# EMMC_Flash_memory.net
KiCad netlist of a schematic drawn in Altium Designer
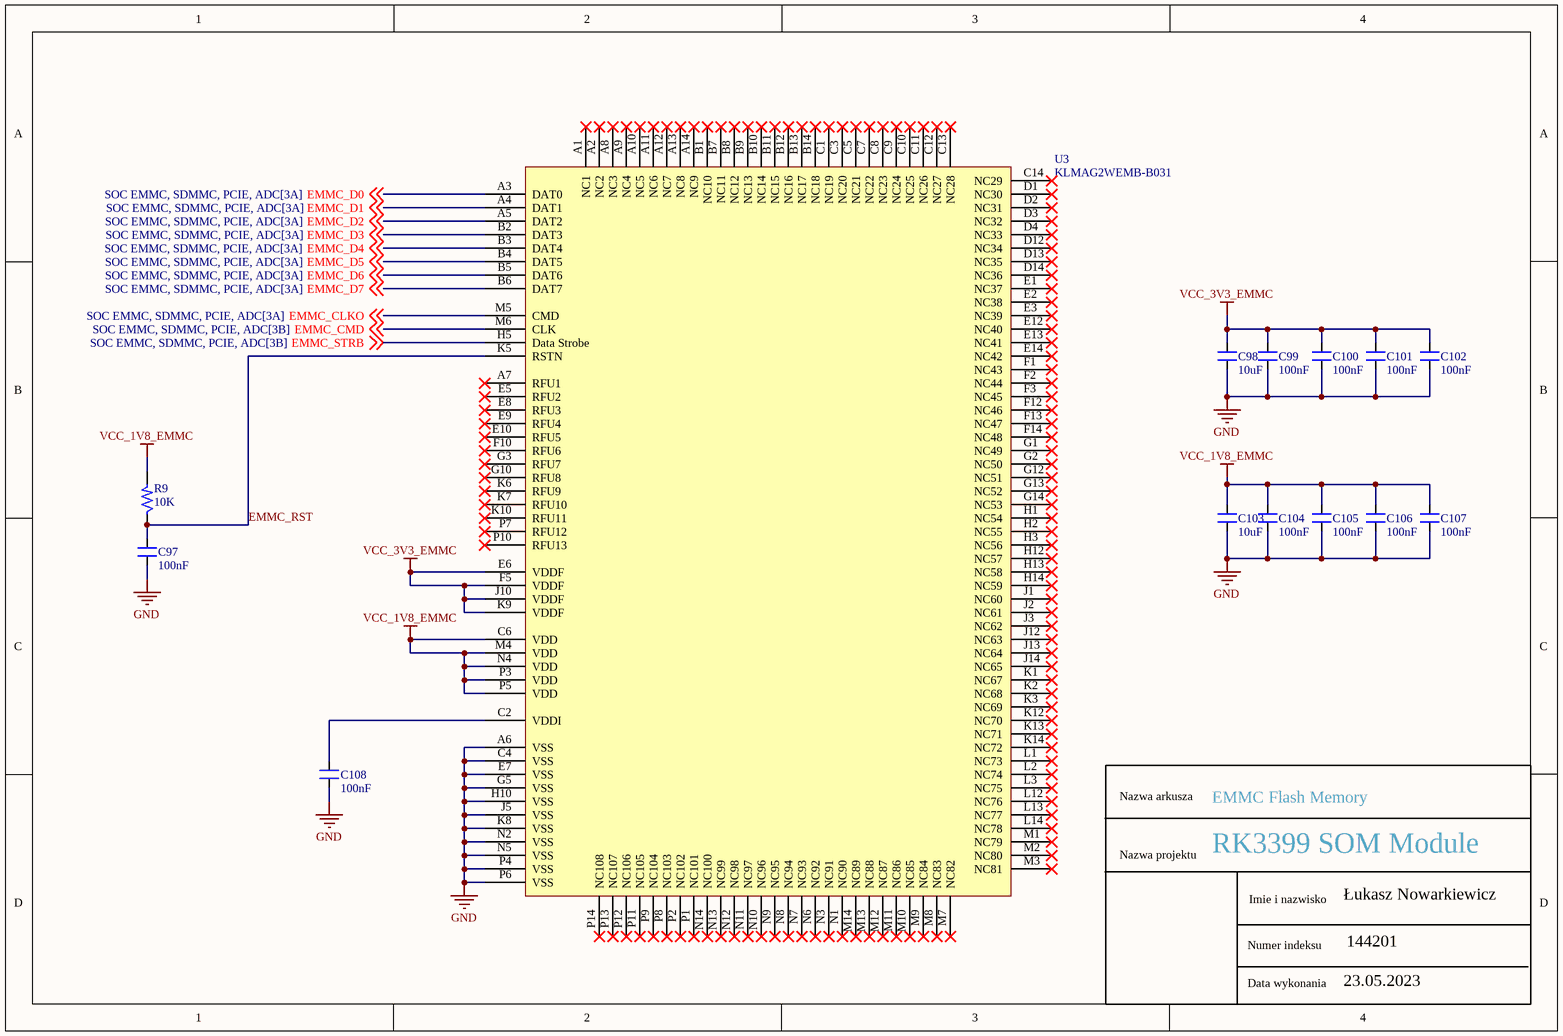
[diagram p0: EMMC Flash memory.SchDoc]

(export (version "E")
  (design (tool "Eeschema 10.0.6"))
  (components
    (comp (ref "C97")
      (value "100nF")
      (footprint "CAP_0402")
      (description "0.1µF ±10% 10V Ceramic Capacitor X7R 0402 (1005 Metric)")
      (fields
        (field (name "MANUFACTURER") "Yageo")
        (field (name "MANUFACTURER PART NUMBER") "CC0402KRX7R6BB104")
      )
      (libsource (lib "EsteemPCB_SOM_Course_intlib") (part "CAP_100nF-10V-10%-0402"))
    )
    (comp (ref "C98")
      (value "10uF")
      (footprint "CAP_0603")
      (description "10µF ±10% 10V Ceramic Capacitor X5R 0603 (1608 Metric)")
      (fields
        (field (name "MANUFACTURER PART NUMBER") "GRM188R61A106KE69J")
        (field (name "MANUFACTURER") "Murata Electronics")
      )
      (libsource (lib "EsteemPCB_SOM_Course_intlib") (part "CAP_10uF-10V-10%-0603"))
    )
    (comp (ref "C99")
      (value "100nF")
      (footprint "CAP_0402")
      (description "0.1µF ±10% 10V Ceramic Capacitor X7R 0402 (1005 Metric)")
      (fields
        (field (name "MANUFACTURER") "Yageo")
        (field (name "MANUFACTURER PART NUMBER") "CC0402KRX7R6BB104")
      )
      (libsource (lib "EsteemPCB_SOM_Course_intlib") (part "CAP_100nF-10V-10%-0402"))
    )
    (comp (ref "C100")
      (value "100nF")
      (footprint "CAP_0402")
      (description "0.1µF ±10% 10V Ceramic Capacitor X7R 0402 (1005 Metric)")
      (fields
        (field (name "MANUFACTURER") "Yageo")
        (field (name "MANUFACTURER PART NUMBER") "CC0402KRX7R6BB104")
      )
      (libsource (lib "EsteemPCB_SOM_Course_intlib") (part "CAP_100nF-10V-10%-0402"))
    )
    (comp (ref "C101")
      (value "100nF")
      (footprint "CAP_0402")
      (description "0.1µF ±10% 10V Ceramic Capacitor X7R 0402 (1005 Metric)")
      (fields
        (field (name "MANUFACTURER") "Yageo")
        (field (name "MANUFACTURER PART NUMBER") "CC0402KRX7R6BB104")
      )
      (libsource (lib "EsteemPCB_SOM_Course_intlib") (part "CAP_100nF-10V-10%-0402"))
    )
    (comp (ref "C102")
      (value "100nF")
      (footprint "CAP_0402")
      (description "0.1µF ±10% 10V Ceramic Capacitor X7R 0402 (1005 Metric)")
      (fields
        (field (name "MANUFACTURER") "Yageo")
        (field (name "MANUFACTURER PART NUMBER") "CC0402KRX7R6BB104")
      )
      (libsource (lib "EsteemPCB_SOM_Course_intlib") (part "CAP_100nF-10V-10%-0402"))
    )
    (comp (ref "C103")
      (value "10uF")
      (footprint "CAP_0603")
      (description "10µF ±10% 10V Ceramic Capacitor X5R 0603 (1608 Metric)")
      (fields
        (field (name "MANUFACTURER PART NUMBER") "GRM188R61A106KE69J")
        (field (name "MANUFACTURER") "Murata Electronics")
      )
      (libsource (lib "EsteemPCB_SOM_Course_intlib") (part "CAP_10uF-10V-10%-0603"))
    )
    (comp (ref "C104")
      (value "100nF")
      (footprint "CAP_0402")
      (description "0.1µF ±10% 10V Ceramic Capacitor X7R 0402 (1005 Metric)")
      (fields
        (field (name "MANUFACTURER") "Yageo")
        (field (name "MANUFACTURER PART NUMBER") "CC0402KRX7R6BB104")
      )
      (libsource (lib "EsteemPCB_SOM_Course_intlib") (part "CAP_100nF-10V-10%-0402"))
    )
    (comp (ref "C105")
      (value "100nF")
      (footprint "CAP_0402")
      (description "0.1µF ±10% 10V Ceramic Capacitor X7R 0402 (1005 Metric)")
      (fields
        (field (name "MANUFACTURER") "Yageo")
        (field (name "MANUFACTURER PART NUMBER") "CC0402KRX7R6BB104")
      )
      (libsource (lib "EsteemPCB_SOM_Course_intlib") (part "CAP_100nF-10V-10%-0402"))
    )
    (comp (ref "C106")
      (value "100nF")
      (footprint "CAP_0402")
      (description "0.1µF ±10% 10V Ceramic Capacitor X7R 0402 (1005 Metric)")
      (fields
        (field (name "MANUFACTURER") "Yageo")
        (field (name "MANUFACTURER PART NUMBER") "CC0402KRX7R6BB104")
      )
      (libsource (lib "EsteemPCB_SOM_Course_intlib") (part "CAP_100nF-10V-10%-0402"))
    )
    (comp (ref "C107")
      (value "100nF")
      (footprint "CAP_0402")
      (description "0.1µF ±10% 10V Ceramic Capacitor X7R 0402 (1005 Metric)")
      (fields
        (field (name "MANUFACTURER") "Yageo")
        (field (name "MANUFACTURER PART NUMBER") "CC0402KRX7R6BB104")
      )
      (libsource (lib "EsteemPCB_SOM_Course_intlib") (part "CAP_100nF-10V-10%-0402"))
    )
    (comp (ref "C108")
      (value "100nF")
      (footprint "CAP_0402")
      (description "0.1µF ±10% 10V Ceramic Capacitor X7R 0402 (1005 Metric)")
      (fields
        (field (name "MANUFACTURER") "Yageo")
        (field (name "MANUFACTURER PART NUMBER") "CC0402KRX7R6BB104")
      )
      (libsource (lib "EsteemPCB_SOM_Course_intlib") (part "CAP_100nF-10V-10%-0402"))
    )
    (comp (ref "R9")
      (value "10K")
      (footprint "RES_0201")
      (description "10 kOhms ±1% 0.05W, 1/20W Chip Resistor 0201 (0603 Metric) Thick Film")
      (fields
        (field (name "MANUFACTURER") "Stackpole Electronics Inc")
        (field (name "MANUFACTURER PART NUMBER") "RMCF0201FT10K0")
      )
      (libsource (lib "EsteemPCB_SOM_Course_intlib") (part "RES_10K-0.05W-1%-0201"))
    )
    (comp (ref "U3")
      (value "KLMAG2WEMB-B031")
      (footprint "BGA153C50P14X14_1150X1300X70")
      (description "16GB NAND Flash Memory")
      (fields (field (name "MANUFACTURER") "Samsung Electronics"))
      (libsource (lib "EsteemPCB_SOM_Course_intlib") (part "IC_KLMAG2WEMB-B031"))
    )
  )
  (nets
    (net (code "1") (name "/EMMC_RST") (class "Default")
      (node (ref "C97") (pin "2") (pinfunction "2_2") (pintype "passive"))
      (node (ref "R9") (pin "1") (pinfunction "1_1") (pintype "passive"))
      (node (ref "U3") (pin "K5") (pinfunction "RSTN_K5") (pintype "passive"))
    )
    (net (code "2") (name "EMMC_CLKO") (class "Default")
      (node (ref "U3") (pin "M5") (pinfunction "CMD_M5") (pintype "passive"))
    )
    (net (code "3") (name "EMMC_CMD") (class "Default")
      (node (ref "U3") (pin "M6") (pinfunction "CLK_M6") (pintype "passive"))
    )
    (net (code "4") (name "EMMC_D0") (class "Default")
      (node (ref "U3") (pin "A3") (pinfunction "DAT0_A3") (pintype "passive"))
    )
    (net (code "5") (name "EMMC_D1") (class "Default")
      (node (ref "U3") (pin "A4") (pinfunction "DAT1_A4") (pintype "passive"))
    )
    (net (code "6") (name "EMMC_D2") (class "Default")
      (node (ref "U3") (pin "A5") (pinfunction "DAT2_A5") (pintype "passive"))
    )
    (net (code "7") (name "EMMC_D3") (class "Default")
      (node (ref "U3") (pin "B2") (pinfunction "DAT3_B2") (pintype "passive"))
    )
    (net (code "8") (name "EMMC_D4") (class "Default")
      (node (ref "U3") (pin "B3") (pinfunction "DAT4_B3") (pintype "passive"))
    )
    (net (code "9") (name "EMMC_D5") (class "Default")
      (node (ref "U3") (pin "B4") (pinfunction "DAT5_B4") (pintype "passive"))
    )
    (net (code "10") (name "EMMC_D6") (class "Default")
      (node (ref "U3") (pin "B5") (pinfunction "DAT6_B5") (pintype "passive"))
    )
    (net (code "11") (name "EMMC_D7") (class "Default")
      (node (ref "U3") (pin "B6") (pinfunction "DAT7_B6") (pintype "passive"))
    )
    (net (code "12") (name "EMMC_STRB") (class "Default")
      (node (ref "U3") (pin "H5") (pinfunction "Data_Strobe_H5") (pintype "passive"))
    )
    (net (code "13") (name "GND") (class "Default")
      (node (ref "C100") (pin "1") (pinfunction "1_1") (pintype "passive"))
      (node (ref "C101") (pin "1") (pinfunction "1_1") (pintype "passive"))
      (node (ref "C102") (pin "1") (pinfunction "1_1") (pintype "passive"))
      (node (ref "C103") (pin "1") (pinfunction "1_1") (pintype "passive"))
      (node (ref "C104") (pin "1") (pinfunction "1_1") (pintype "passive"))
      (node (ref "C105") (pin "1") (pinfunction "1_1") (pintype "passive"))
      (node (ref "C106") (pin "1") (pinfunction "1_1") (pintype "passive"))
      (node (ref "C107") (pin "1") (pinfunction "1_1") (pintype "passive"))
      (node (ref "C108") (pin "1") (pinfunction "1_1") (pintype "passive"))
      (node (ref "C97") (pin "1") (pinfunction "1_1") (pintype "passive"))
      (node (ref "C98") (pin "1") (pinfunction "1_1") (pintype "passive"))
      (node (ref "C99") (pin "1") (pinfunction "1_1") (pintype "passive"))
      (node (ref "U3") (pin "A6") (pinfunction "VSS_A6") (pintype "passive"))
      (node (ref "U3") (pin "C4") (pinfunction "VSS_C4") (pintype "passive"))
      (node (ref "U3") (pin "E7") (pinfunction "VSS_E7") (pintype "passive"))
      (node (ref "U3") (pin "G5") (pinfunction "VSS_G5") (pintype "passive"))
      (node (ref "U3") (pin "H10") (pinfunction "VSS_H10") (pintype "passive"))
      (node (ref "U3") (pin "J5") (pinfunction "VSS_J5") (pintype "passive"))
      (node (ref "U3") (pin "K8") (pinfunction "VSS_K8") (pintype "passive"))
      (node (ref "U3") (pin "N2") (pinfunction "VSS_N2") (pintype "passive"))
      (node (ref "U3") (pin "N5") (pinfunction "VSS_N5") (pintype "passive"))
      (node (ref "U3") (pin "P4") (pinfunction "VSS_P4") (pintype "passive"))
      (node (ref "U3") (pin "P6") (pinfunction "VSS_P6") (pintype "passive"))
    )
    (net (code "14") (name "Net-(U3-VDDI)") (class "Default")
      (node (ref "C108") (pin "2") (pinfunction "2_2") (pintype "passive"))
      (node (ref "U3") (pin "C2") (pinfunction "VDDI_C2") (pintype "passive"))
    )
    (net (code "15") (name "VCC_1V8_EMMC") (class "Default")
      (node (ref "C103") (pin "2") (pinfunction "2_2") (pintype "passive"))
      (node (ref "C104") (pin "2") (pinfunction "2_2") (pintype "passive"))
      (node (ref "C105") (pin "2") (pinfunction "2_2") (pintype "passive"))
      (node (ref "C106") (pin "2") (pinfunction "2_2") (pintype "passive"))
      (node (ref "C107") (pin "2") (pinfunction "2_2") (pintype "passive"))
      (node (ref "R9") (pin "2") (pinfunction "2_2") (pintype "passive"))
      (node (ref "U3") (pin "C6") (pinfunction "VDD_C6") (pintype "passive"))
      (node (ref "U3") (pin "M4") (pinfunction "VDD_M4") (pintype "passive"))
      (node (ref "U3") (pin "N4") (pinfunction "VDD_N4") (pintype "passive"))
      (node (ref "U3") (pin "P3") (pinfunction "VDD_P3") (pintype "passive"))
      (node (ref "U3") (pin "P5") (pinfunction "VDD_P5") (pintype "passive"))
    )
    (net (code "16") (name "VCC_3V3_EMMC") (class "Default")
      (node (ref "C100") (pin "2") (pinfunction "2_2") (pintype "passive"))
      (node (ref "C101") (pin "2") (pinfunction "2_2") (pintype "passive"))
      (node (ref "C102") (pin "2") (pinfunction "2_2") (pintype "passive"))
      (node (ref "C98") (pin "2") (pinfunction "2_2") (pintype "passive"))
      (node (ref "C99") (pin "2") (pinfunction "2_2") (pintype "passive"))
      (node (ref "U3") (pin "E6") (pinfunction "VDDF_E6") (pintype "passive"))
      (node (ref "U3") (pin "F5") (pinfunction "VDDF_F5") (pintype "passive"))
      (node (ref "U3") (pin "J10") (pinfunction "VDDF_J10") (pintype "passive"))
      (node (ref "U3") (pin "K9") (pinfunction "VDDF_K9") (pintype "passive"))
    )
    (net (code "17") (name "unconnected-(U3-NC1-PadA1)") (class "Default")
      (node (ref "U3") (pin "A1") (pinfunction "NC1_A1") (pintype "passive+no_connect"))
    )
    (net (code "18") (name "unconnected-(U3-NC2-PadA2)") (class "Default")
      (node (ref "U3") (pin "A2") (pinfunction "NC2_A2") (pintype "passive+no_connect"))
    )
    (net (code "19") (name "unconnected-(U3-NC3-PadA8)") (class "Default")
      (node (ref "U3") (pin "A8") (pinfunction "NC3_A8") (pintype "passive+no_connect"))
    )
    (net (code "20") (name "unconnected-(U3-NC4-PadA9)") (class "Default")
      (node (ref "U3") (pin "A9") (pinfunction "NC4_A9") (pintype "passive+no_connect"))
    )
    (net (code "21") (name "unconnected-(U3-NC5-PadA10)") (class "Default")
      (node (ref "U3") (pin "A10") (pinfunction "NC5_A10") (pintype "passive+no_connect"))
    )
    (net (code "22") (name "unconnected-(U3-NC6-PadA11)") (class "Default")
      (node (ref "U3") (pin "A11") (pinfunction "NC6_A11") (pintype "passive+no_connect"))
    )
    (net (code "23") (name "unconnected-(U3-NC7-PadA12)") (class "Default")
      (node (ref "U3") (pin "A12") (pinfunction "NC7_A12") (pintype "passive+no_connect"))
    )
    (net (code "24") (name "unconnected-(U3-NC8-PadA13)") (class "Default")
      (node (ref "U3") (pin "A13") (pinfunction "NC8_A13") (pintype "passive+no_connect"))
    )
    (net (code "25") (name "unconnected-(U3-NC9-PadA14)") (class "Default")
      (node (ref "U3") (pin "A14") (pinfunction "NC9_A14") (pintype "passive+no_connect"))
    )
    (net (code "26") (name "unconnected-(U3-NC10-PadB1)") (class "Default")
      (node (ref "U3") (pin "B1") (pinfunction "NC10_B1") (pintype "passive+no_connect"))
    )
    (net (code "27") (name "unconnected-(U3-NC11-PadB7)") (class "Default")
      (node (ref "U3") (pin "B7") (pinfunction "NC11_B7") (pintype "passive+no_connect"))
    )
    (net (code "28") (name "unconnected-(U3-NC12-PadB8)") (class "Default")
      (node (ref "U3") (pin "B8") (pinfunction "NC12_B8") (pintype "passive+no_connect"))
    )
    (net (code "29") (name "unconnected-(U3-NC13-PadB9)") (class "Default")
      (node (ref "U3") (pin "B9") (pinfunction "NC13_B9") (pintype "passive+no_connect"))
    )
    (net (code "30") (name "unconnected-(U3-NC14-PadB10)") (class "Default")
      (node (ref "U3") (pin "B10") (pinfunction "NC14_B10") (pintype "passive+no_connect"))
    )
    (net (code "31") (name "unconnected-(U3-NC15-PadB11)") (class "Default")
      (node (ref "U3") (pin "B11") (pinfunction "NC15_B11") (pintype "passive+no_connect"))
    )
    (net (code "32") (name "unconnected-(U3-NC16-PadB12)") (class "Default")
      (node (ref "U3") (pin "B12") (pinfunction "NC16_B12") (pintype "passive+no_connect"))
    )
    (net (code "33") (name "unconnected-(U3-NC17-PadB13)") (class "Default")
      (node (ref "U3") (pin "B13") (pinfunction "NC17_B13") (pintype "passive+no_connect"))
    )
    (net (code "34") (name "unconnected-(U3-NC18-PadB14)") (class "Default")
      (node (ref "U3") (pin "B14") (pinfunction "NC18_B14") (pintype "passive+no_connect"))
    )
    (net (code "35") (name "unconnected-(U3-NC19-PadC1)") (class "Default")
      (node (ref "U3") (pin "C1") (pinfunction "NC19_C1") (pintype "passive+no_connect"))
    )
    (net (code "36") (name "unconnected-(U3-NC20-PadC3)") (class "Default")
      (node (ref "U3") (pin "C3") (pinfunction "NC20_C3") (pintype "passive+no_connect"))
    )
    (net (code "37") (name "unconnected-(U3-NC21-PadC5)") (class "Default")
      (node (ref "U3") (pin "C5") (pinfunction "NC21_C5") (pintype "passive+no_connect"))
    )
    (net (code "38") (name "unconnected-(U3-NC22-PadC7)") (class "Default")
      (node (ref "U3") (pin "C7") (pinfunction "NC22_C7") (pintype "passive+no_connect"))
    )
    (net (code "39") (name "unconnected-(U3-NC23-PadC8)") (class "Default")
      (node (ref "U3") (pin "C8") (pinfunction "NC23_C8") (pintype "passive+no_connect"))
    )
    (net (code "40") (name "unconnected-(U3-NC24-PadC9)") (class "Default")
      (node (ref "U3") (pin "C9") (pinfunction "NC24_C9") (pintype "passive+no_connect"))
    )
    (net (code "41") (name "unconnected-(U3-NC25-PadC10)") (class "Default")
      (node (ref "U3") (pin "C10") (pinfunction "NC25_C10") (pintype "passive+no_connect"))
    )
    (net (code "42") (name "unconnected-(U3-NC26-PadC11)") (class "Default")
      (node (ref "U3") (pin "C11") (pinfunction "NC26_C11") (pintype "passive+no_connect"))
    )
    (net (code "43") (name "unconnected-(U3-NC27-PadC12)") (class "Default")
      (node (ref "U3") (pin "C12") (pinfunction "NC27_C12") (pintype "passive+no_connect"))
    )
    (net (code "44") (name "unconnected-(U3-NC28-PadC13)") (class "Default")
      (node (ref "U3") (pin "C13") (pinfunction "NC28_C13") (pintype "passive+no_connect"))
    )
    (net (code "45") (name "unconnected-(U3-NC29-PadC14)") (class "Default")
      (node (ref "U3") (pin "C14") (pinfunction "NC29_C14") (pintype "passive+no_connect"))
    )
    (net (code "46") (name "unconnected-(U3-NC30-PadD1)") (class "Default")
      (node (ref "U3") (pin "D1") (pinfunction "NC30_D1") (pintype "passive+no_connect"))
    )
    (net (code "47") (name "unconnected-(U3-NC31-PadD2)") (class "Default")
      (node (ref "U3") (pin "D2") (pinfunction "NC31_D2") (pintype "passive+no_connect"))
    )
    (net (code "48") (name "unconnected-(U3-NC32-PadD3)") (class "Default")
      (node (ref "U3") (pin "D3") (pinfunction "NC32_D3") (pintype "passive+no_connect"))
    )
    (net (code "49") (name "unconnected-(U3-NC33-PadD4)") (class "Default")
      (node (ref "U3") (pin "D4") (pinfunction "NC33_D4") (pintype "passive+no_connect"))
    )
    (net (code "50") (name "unconnected-(U3-NC34-PadD12)") (class "Default")
      (node (ref "U3") (pin "D12") (pinfunction "NC34_D12") (pintype "passive+no_connect"))
    )
    (net (code "51") (name "unconnected-(U3-NC35-PadD13)") (class "Default")
      (node (ref "U3") (pin "D13") (pinfunction "NC35_D13") (pintype "passive+no_connect"))
    )
    (net (code "52") (name "unconnected-(U3-NC36-PadD14)") (class "Default")
      (node (ref "U3") (pin "D14") (pinfunction "NC36_D14") (pintype "passive+no_connect"))
    )
    (net (code "53") (name "unconnected-(U3-NC37-PadE1)") (class "Default")
      (node (ref "U3") (pin "E1") (pinfunction "NC37_E1") (pintype "passive+no_connect"))
    )
    (net (code "54") (name "unconnected-(U3-NC38-PadE2)") (class "Default")
      (node (ref "U3") (pin "E2") (pinfunction "NC38_E2") (pintype "passive+no_connect"))
    )
    (net (code "55") (name "unconnected-(U3-NC39-PadE3)") (class "Default")
      (node (ref "U3") (pin "E3") (pinfunction "NC39_E3") (pintype "passive+no_connect"))
    )
    (net (code "56") (name "unconnected-(U3-NC40-PadE12)") (class "Default")
      (node (ref "U3") (pin "E12") (pinfunction "NC40_E12") (pintype "passive+no_connect"))
    )
    (net (code "57") (name "unconnected-(U3-NC41-PadE13)") (class "Default")
      (node (ref "U3") (pin "E13") (pinfunction "NC41_E13") (pintype "passive+no_connect"))
    )
    (net (code "58") (name "unconnected-(U3-NC42-PadE14)") (class "Default")
      (node (ref "U3") (pin "E14") (pinfunction "NC42_E14") (pintype "passive+no_connect"))
    )
    (net (code "59") (name "unconnected-(U3-NC43-PadF1)") (class "Default")
      (node (ref "U3") (pin "F1") (pinfunction "NC43_F1") (pintype "passive+no_connect"))
    )
    (net (code "60") (name "unconnected-(U3-NC44-PadF2)") (class "Default")
      (node (ref "U3") (pin "F2") (pinfunction "NC44_F2") (pintype "passive+no_connect"))
    )
    (net (code "61") (name "unconnected-(U3-NC45-PadF3)") (class "Default")
      (node (ref "U3") (pin "F3") (pinfunction "NC45_F3") (pintype "passive+no_connect"))
    )
    (net (code "62") (name "unconnected-(U3-NC46-PadF12)") (class "Default")
      (node (ref "U3") (pin "F12") (pinfunction "NC46_F12") (pintype "passive+no_connect"))
    )
    (net (code "63") (name "unconnected-(U3-NC47-PadF13)") (class "Default")
      (node (ref "U3") (pin "F13") (pinfunction "NC47_F13") (pintype "passive+no_connect"))
    )
    (net (code "64") (name "unconnected-(U3-NC48-PadF14)") (class "Default")
      (node (ref "U3") (pin "F14") (pinfunction "NC48_F14") (pintype "passive+no_connect"))
    )
    (net (code "65") (name "unconnected-(U3-NC49-PadG1)") (class "Default")
      (node (ref "U3") (pin "G1") (pinfunction "NC49_G1") (pintype "passive+no_connect"))
    )
    (net (code "66") (name "unconnected-(U3-NC50-PadG2)") (class "Default")
      (node (ref "U3") (pin "G2") (pinfunction "NC50_G2") (pintype "passive+no_connect"))
    )
    (net (code "67") (name "unconnected-(U3-NC51-PadG12)") (class "Default")
      (node (ref "U3") (pin "G12") (pinfunction "NC51_G12") (pintype "passive+no_connect"))
    )
    (net (code "68") (name "unconnected-(U3-NC52-PadG13)") (class "Default")
      (node (ref "U3") (pin "G13") (pinfunction "NC52_G13") (pintype "passive+no_connect"))
    )
    (net (code "69") (name "unconnected-(U3-NC53-PadG14)") (class "Default")
      (node (ref "U3") (pin "G14") (pinfunction "NC53_G14") (pintype "passive+no_connect"))
    )
    (net (code "70") (name "unconnected-(U3-NC54-PadH1)") (class "Default")
      (node (ref "U3") (pin "H1") (pinfunction "NC54_H1") (pintype "passive+no_connect"))
    )
    (net (code "71") (name "unconnected-(U3-NC55-PadH2)") (class "Default")
      (node (ref "U3") (pin "H2") (pinfunction "NC55_H2") (pintype "passive+no_connect"))
    )
    (net (code "72") (name "unconnected-(U3-NC56-PadH3)") (class "Default")
      (node (ref "U3") (pin "H3") (pinfunction "NC56_H3") (pintype "passive+no_connect"))
    )
    (net (code "73") (name "unconnected-(U3-NC57-PadH12)") (class "Default")
      (node (ref "U3") (pin "H12") (pinfunction "NC57_H12") (pintype "passive+no_connect"))
    )
    (net (code "74") (name "unconnected-(U3-NC58-PadH13)") (class "Default")
      (node (ref "U3") (pin "H13") (pinfunction "NC58_H13") (pintype "passive+no_connect"))
    )
    (net (code "75") (name "unconnected-(U3-NC59-PadH14)") (class "Default")
      (node (ref "U3") (pin "H14") (pinfunction "NC59_H14") (pintype "passive+no_connect"))
    )
    (net (code "76") (name "unconnected-(U3-NC60-PadJ1)") (class "Default")
      (node (ref "U3") (pin "J1") (pinfunction "NC60_J1") (pintype "passive+no_connect"))
    )
    (net (code "77") (name "unconnected-(U3-NC61-PadJ2)") (class "Default")
      (node (ref "U3") (pin "J2") (pinfunction "NC61_J2") (pintype "passive+no_connect"))
    )
    (net (code "78") (name "unconnected-(U3-NC62-PadJ3)") (class "Default")
      (node (ref "U3") (pin "J3") (pinfunction "NC62_J3") (pintype "passive+no_connect"))
    )
    (net (code "79") (name "unconnected-(U3-NC63-PadJ12)") (class "Default")
      (node (ref "U3") (pin "J12") (pinfunction "NC63_J12") (pintype "passive+no_connect"))
    )
    (net (code "80") (name "unconnected-(U3-NC64-PadJ13)") (class "Default")
      (node (ref "U3") (pin "J13") (pinfunction "NC64_J13") (pintype "passive+no_connect"))
    )
    (net (code "81") (name "unconnected-(U3-NC65-PadJ14)") (class "Default")
      (node (ref "U3") (pin "J14") (pinfunction "NC65_J14") (pintype "passive+no_connect"))
    )
    (net (code "82") (name "unconnected-(U3-NC67-PadK1)") (class "Default")
      (node (ref "U3") (pin "K1") (pinfunction "NC67_K1") (pintype "passive+no_connect"))
    )
    (net (code "83") (name "unconnected-(U3-NC68-PadK2)") (class "Default")
      (node (ref "U3") (pin "K2") (pinfunction "NC68_K2") (pintype "passive+no_connect"))
    )
    (net (code "84") (name "unconnected-(U3-NC69-PadK3)") (class "Default")
      (node (ref "U3") (pin "K3") (pinfunction "NC69_K3") (pintype "passive+no_connect"))
    )
    (net (code "85") (name "unconnected-(U3-NC70-PadK12)") (class "Default")
      (node (ref "U3") (pin "K12") (pinfunction "NC70_K12") (pintype "passive+no_connect"))
    )
    (net (code "86") (name "unconnected-(U3-NC71-PadK13)") (class "Default")
      (node (ref "U3") (pin "K13") (pinfunction "NC71_K13") (pintype "passive+no_connect"))
    )
    (net (code "87") (name "unconnected-(U3-NC72-PadK14)") (class "Default")
      (node (ref "U3") (pin "K14") (pinfunction "NC72_K14") (pintype "passive+no_connect"))
    )
    (net (code "88") (name "unconnected-(U3-NC73-PadL1)") (class "Default")
      (node (ref "U3") (pin "L1") (pinfunction "NC73_L1") (pintype "passive+no_connect"))
    )
    (net (code "89") (name "unconnected-(U3-NC74-PadL2)") (class "Default")
      (node (ref "U3") (pin "L2") (pinfunction "NC74_L2") (pintype "passive+no_connect"))
    )
    (net (code "90") (name "unconnected-(U3-NC75-PadL3)") (class "Default")
      (node (ref "U3") (pin "L3") (pinfunction "NC75_L3") (pintype "passive+no_connect"))
    )
    (net (code "91") (name "unconnected-(U3-NC76-PadL12)") (class "Default")
      (node (ref "U3") (pin "L12") (pinfunction "NC76_L12") (pintype "passive+no_connect"))
    )
    (net (code "92") (name "unconnected-(U3-NC77-PadL13)") (class "Default")
      (node (ref "U3") (pin "L13") (pinfunction "NC77_L13") (pintype "passive+no_connect"))
    )
    (net (code "93") (name "unconnected-(U3-NC78-PadL14)") (class "Default")
      (node (ref "U3") (pin "L14") (pinfunction "NC78_L14") (pintype "passive+no_connect"))
    )
    (net (code "94") (name "unconnected-(U3-NC79-PadM1)") (class "Default")
      (node (ref "U3") (pin "M1") (pinfunction "NC79_M1") (pintype "passive+no_connect"))
    )
    (net (code "95") (name "unconnected-(U3-NC80-PadM2)") (class "Default")
      (node (ref "U3") (pin "M2") (pinfunction "NC80_M2") (pintype "passive+no_connect"))
    )
    (net (code "96") (name "unconnected-(U3-NC81-PadM3)") (class "Default")
      (node (ref "U3") (pin "M3") (pinfunction "NC81_M3") (pintype "passive+no_connect"))
    )
    (net (code "97") (name "unconnected-(U3-NC82-PadM7)") (class "Default")
      (node (ref "U3") (pin "M7") (pinfunction "NC82_M7") (pintype "passive+no_connect"))
    )
    (net (code "98") (name "unconnected-(U3-NC83-PadM8)") (class "Default")
      (node (ref "U3") (pin "M8") (pinfunction "NC83_M8") (pintype "passive+no_connect"))
    )
    (net (code "99") (name "unconnected-(U3-NC84-PadM9)") (class "Default")
      (node (ref "U3") (pin "M9") (pinfunction "NC84_M9") (pintype "passive+no_connect"))
    )
    (net (code "100") (name "unconnected-(U3-NC85-PadM10)") (class "Default")
      (node (ref "U3") (pin "M10") (pinfunction "NC85_M10") (pintype "passive+no_connect"))
    )
    (net (code "101") (name "unconnected-(U3-NC86-PadM11)") (class "Default")
      (node (ref "U3") (pin "M11") (pinfunction "NC86_M11") (pintype "passive+no_connect"))
    )
    (net (code "102") (name "unconnected-(U3-NC87-PadM12)") (class "Default")
      (node (ref "U3") (pin "M12") (pinfunction "NC87_M12") (pintype "passive+no_connect"))
    )
    (net (code "103") (name "unconnected-(U3-NC88-PadM13)") (class "Default")
      (node (ref "U3") (pin "M13") (pinfunction "NC88_M13") (pintype "passive+no_connect"))
    )
    (net (code "104") (name "unconnected-(U3-NC89-PadM14)") (class "Default")
      (node (ref "U3") (pin "M14") (pinfunction "NC89_M14") (pintype "passive+no_connect"))
    )
    (net (code "105") (name "unconnected-(U3-NC90-PadN1)") (class "Default")
      (node (ref "U3") (pin "N1") (pinfunction "NC90_N1") (pintype "passive+no_connect"))
    )
    (net (code "106") (name "unconnected-(U3-NC91-PadN3)") (class "Default")
      (node (ref "U3") (pin "N3") (pinfunction "NC91_N3") (pintype "passive+no_connect"))
    )
    (net (code "107") (name "unconnected-(U3-NC92-PadN6)") (class "Default")
      (node (ref "U3") (pin "N6") (pinfunction "NC92_N6") (pintype "passive+no_connect"))
    )
    (net (code "108") (name "unconnected-(U3-NC93-PadN7)") (class "Default")
      (node (ref "U3") (pin "N7") (pinfunction "NC93_N7") (pintype "passive+no_connect"))
    )
    (net (code "109") (name "unconnected-(U3-NC94-PadN8)") (class "Default")
      (node (ref "U3") (pin "N8") (pinfunction "NC94_N8") (pintype "passive+no_connect"))
    )
    (net (code "110") (name "unconnected-(U3-NC95-PadN9)") (class "Default")
      (node (ref "U3") (pin "N9") (pinfunction "NC95_N9") (pintype "passive+no_connect"))
    )
    (net (code "111") (name "unconnected-(U3-NC96-PadN10)") (class "Default")
      (node (ref "U3") (pin "N10") (pinfunction "NC96_N10") (pintype "passive+no_connect"))
    )
    (net (code "112") (name "unconnected-(U3-NC97-PadN11)") (class "Default")
      (node (ref "U3") (pin "N11") (pinfunction "NC97_N11") (pintype "passive+no_connect"))
    )
    (net (code "113") (name "unconnected-(U3-NC98-PadN12)") (class "Default")
      (node (ref "U3") (pin "N12") (pinfunction "NC98_N12") (pintype "passive+no_connect"))
    )
    (net (code "114") (name "unconnected-(U3-NC99-PadN13)") (class "Default")
      (node (ref "U3") (pin "N13") (pinfunction "NC99_N13") (pintype "passive+no_connect"))
    )
    (net (code "115") (name "unconnected-(U3-NC100-PadN14)") (class "Default")
      (node (ref "U3") (pin "N14") (pinfunction "NC100_N14") (pintype "passive+no_connect"))
    )
    (net (code "116") (name "unconnected-(U3-NC101-PadP1)") (class "Default")
      (node (ref "U3") (pin "P1") (pinfunction "NC101_P1") (pintype "passive+no_connect"))
    )
    (net (code "117") (name "unconnected-(U3-NC102-PadP2)") (class "Default")
      (node (ref "U3") (pin "P2") (pinfunction "NC102_P2") (pintype "passive+no_connect"))
    )
    (net (code "118") (name "unconnected-(U3-NC103-PadP8)") (class "Default")
      (node (ref "U3") (pin "P8") (pinfunction "NC103_P8") (pintype "passive+no_connect"))
    )
    (net (code "119") (name "unconnected-(U3-NC104-PadP9)") (class "Default")
      (node (ref "U3") (pin "P9") (pinfunction "NC104_P9") (pintype "passive+no_connect"))
    )
    (net (code "120") (name "unconnected-(U3-NC105-PadP11)") (class "Default")
      (node (ref "U3") (pin "P11") (pinfunction "NC105_P11") (pintype "passive+no_connect"))
    )
    (net (code "121") (name "unconnected-(U3-NC106-PadP12)") (class "Default")
      (node (ref "U3") (pin "P12") (pinfunction "NC106_P12") (pintype "passive+no_connect"))
    )
    (net (code "122") (name "unconnected-(U3-NC107-PadP13)") (class "Default")
      (node (ref "U3") (pin "P13") (pinfunction "NC107_P13") (pintype "passive+no_connect"))
    )
    (net (code "123") (name "unconnected-(U3-NC108-PadP14)") (class "Default")
      (node (ref "U3") (pin "P14") (pinfunction "NC108_P14") (pintype "passive+no_connect"))
    )
    (net (code "124") (name "unconnected-(U3-RFU1-PadA7)") (class "Default")
      (node (ref "U3") (pin "A7") (pinfunction "RFU1_A7") (pintype "passive+no_connect"))
    )
    (net (code "125") (name "unconnected-(U3-RFU2-PadE5)") (class "Default")
      (node (ref "U3") (pin "E5") (pinfunction "RFU2_E5") (pintype "passive+no_connect"))
    )
    (net (code "126") (name "unconnected-(U3-RFU3-PadE8)") (class "Default")
      (node (ref "U3") (pin "E8") (pinfunction "RFU3_E8") (pintype "passive+no_connect"))
    )
    (net (code "127") (name "unconnected-(U3-RFU4-PadE9)") (class "Default")
      (node (ref "U3") (pin "E9") (pinfunction "RFU4_E9") (pintype "passive+no_connect"))
    )
    (net (code "128") (name "unconnected-(U3-RFU5-PadE10)") (class "Default")
      (node (ref "U3") (pin "E10") (pinfunction "RFU5_E10") (pintype "passive+no_connect"))
    )
    (net (code "129") (name "unconnected-(U3-RFU6-PadF10)") (class "Default")
      (node (ref "U3") (pin "F10") (pinfunction "RFU6_F10") (pintype "passive+no_connect"))
    )
    (net (code "130") (name "unconnected-(U3-RFU7-PadG3)") (class "Default")
      (node (ref "U3") (pin "G3") (pinfunction "RFU7_G3") (pintype "passive+no_connect"))
    )
    (net (code "131") (name "unconnected-(U3-RFU8-PadG10)") (class "Default")
      (node (ref "U3") (pin "G10") (pinfunction "RFU8_G10") (pintype "passive+no_connect"))
    )
    (net (code "132") (name "unconnected-(U3-RFU9-PadK6)") (class "Default")
      (node (ref "U3") (pin "K6") (pinfunction "RFU9_K6") (pintype "passive+no_connect"))
    )
    (net (code "133") (name "unconnected-(U3-RFU10-PadK7)") (class "Default")
      (node (ref "U3") (pin "K7") (pinfunction "RFU10_K7") (pintype "passive+no_connect"))
    )
    (net (code "134") (name "unconnected-(U3-RFU11-PadK10)") (class "Default")
      (node (ref "U3") (pin "K10") (pinfunction "RFU11_K10") (pintype "passive+no_connect"))
    )
    (net (code "135") (name "unconnected-(U3-RFU12-PadP7)") (class "Default")
      (node (ref "U3") (pin "P7") (pinfunction "RFU12_P7") (pintype "passive+no_connect"))
    )
    (net (code "136") (name "unconnected-(U3-RFU13-PadP10)") (class "Default")
      (node (ref "U3") (pin "P10") (pinfunction "RFU13_P10") (pintype "passive+no_connect"))
    )
  )
)
